# MAX4070_roznicowy_analog.net
KiCad netlist of a schematic drawn in EAGLE
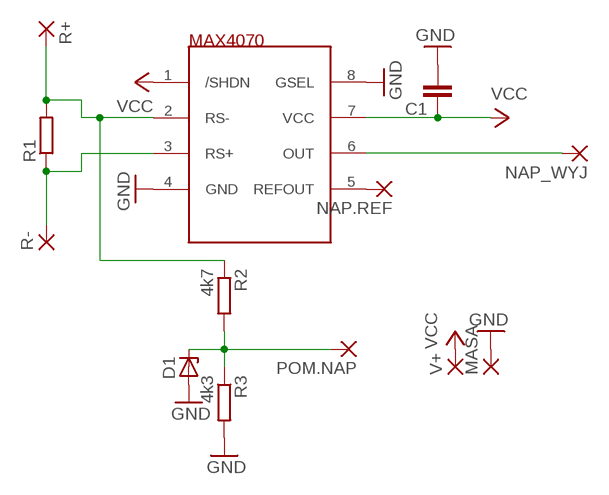
[diagram p0: schematic, sheet 1]

(export (version "E")
  (design (tool "Eeschema 10.0.6"))
  (components
    (comp (ref "C1")
      (value "C-EUC1206")
      (footprint "eagle-import:C1206")
      (libsource (lib "eagle-import") (part "C-EUC1206"))
    )
    (comp (ref "D1")
      (value "ZENER-DIODESOD80C")
      (footprint "eagle-import:SOD80C")
      (libsource (lib "eagle-import") (part "ZENER-DIODESOD80C"))
    )
    (comp (ref "MASA")
      (value "1,6/0,8")
      (footprint "eagle-import:1,6_0,8")
      (libsource (lib "eagle-import") (part "1,6/0,8"))
    )
    (comp (ref "NAP.REF")
      (value "1,6/0,8")
      (footprint "eagle-import:1,6_0,8")
      (libsource (lib "eagle-import") (part "1,6/0,8"))
    )
    (comp (ref "NAP_WYJ")
      (value "1,6/0,8")
      (footprint "eagle-import:1,6_0,8")
      (libsource (lib "eagle-import") (part "1,6/0,8"))
    )
    (comp (ref "POM.NAP")
      (value "1,6/0,8")
      (footprint "eagle-import:1,6_0,8")
      (libsource (lib "eagle-import") (part "1,6/0,8"))
    )
    (comp (ref "R+")
      (value "1,6/0,8")
      (footprint "eagle-import:1,6_0,8")
      (libsource (lib "eagle-import") (part "1,6/0,8"))
    )
    (comp (ref "R-")
      (value "1,6/0,8")
      (footprint "eagle-import:1,6_0,8")
      (libsource (lib "eagle-import") (part "1,6/0,8"))
    )
    (comp (ref "R1")
      (value "R-EU_0617/22")
      (footprint "eagle-import:0617_22")
      (libsource (lib "eagle-import") (part "R-EU_0617/22"))
    )
    (comp (ref "R2")
      (value "4k7")
      (footprint "eagle-import:0207_10")
      (libsource (lib "eagle-import") (part "R-EU_0207/10"))
    )
    (comp (ref "R3")
      (value "4k3")
      (footprint "eagle-import:0207_10")
      (libsource (lib "eagle-import") (part "R-EU_0207/10"))
    )
    (comp (ref "U$1")
      (value "MAX4070")
      (footprint "eagle-import:UMAX8")
      (libsource (lib "eagle-import") (part "MAX4070"))
    )
    (comp (ref "V+")
      (value "1,6/0,8")
      (footprint "eagle-import:1,6_0,8")
      (libsource (lib "eagle-import") (part "1,6/0,8"))
    )
  )
  (nets
    (net (code "1") (name "GND") (class "Default")
      (node (ref "C1") (pin "2") (pinfunction "2_2") (pintype "passive"))
      (node (ref "D1") (pin "A") (pinfunction "A_A") (pintype "passive"))
      (node (ref "MASA") (pin "1") (pinfunction "P_1") (pintype "passive"))
      (node (ref "R3") (pin "2") (pinfunction "2_2") (pintype "passive"))
      (node (ref "U$1") (pin "4") (pinfunction "GND_4") (pintype "bidirectional"))
      (node (ref "U$1") (pin "8") (pinfunction "GSEL_8") (pintype "bidirectional"))
    )
    (net (code "2") (name "Net-(NAP.REF-P)") (class "Default")
      (node (ref "NAP.REF") (pin "1") (pinfunction "P_1") (pintype "passive"))
      (node (ref "U$1") (pin "5") (pinfunction "REFOUT_5") (pintype "bidirectional"))
    )
    (net (code "3") (name "Net-(NAP_WYJ-P)") (class "Default")
      (node (ref "NAP_WYJ") (pin "1") (pinfunction "P_1") (pintype "passive"))
      (node (ref "U$1") (pin "6") (pinfunction "OUT_6") (pintype "bidirectional"))
    )
    (net (code "4") (name "Net-(POM.NAP-P)") (class "Default")
      (node (ref "D1") (pin "C") (pinfunction "C_C") (pintype "passive"))
      (node (ref "POM.NAP") (pin "1") (pinfunction "P_1") (pintype "passive"))
      (node (ref "R2") (pin "2") (pinfunction "2_2") (pintype "passive"))
      (node (ref "R3") (pin "1") (pinfunction "1_1") (pintype "passive"))
    )
    (net (code "5") (name "Net-(R+-P)") (class "Default")
      (node (ref "R+") (pin "1") (pinfunction "P_1") (pintype "passive"))
      (node (ref "R1") (pin "2") (pinfunction "2_2") (pintype "passive"))
      (node (ref "R2") (pin "1") (pinfunction "1_1") (pintype "passive"))
      (node (ref "U$1") (pin "2") (pinfunction "RS-_2") (pintype "bidirectional"))
    )
    (net (code "6") (name "Net-(R--P)") (class "Default")
      (node (ref "R-") (pin "1") (pinfunction "P_1") (pintype "passive"))
      (node (ref "R1") (pin "1") (pinfunction "1_1") (pintype "passive"))
      (node (ref "U$1") (pin "3") (pinfunction "RS+_3") (pintype "bidirectional"))
    )
    (net (code "7") (name "VCC") (class "Default")
      (node (ref "C1") (pin "1") (pinfunction "1_1") (pintype "passive"))
      (node (ref "U$1") (pin "1") (pinfunction "/SHDN_1") (pintype "bidirectional"))
      (node (ref "U$1") (pin "7") (pinfunction "VCC_7") (pintype "bidirectional"))
      (node (ref "V+") (pin "1") (pinfunction "P_1") (pintype "passive"))
    )
  )
)
